# 4L60E_Controller_SMD_CONNECTOR.net
KiCad netlist of a schematic drawn in EAGLE
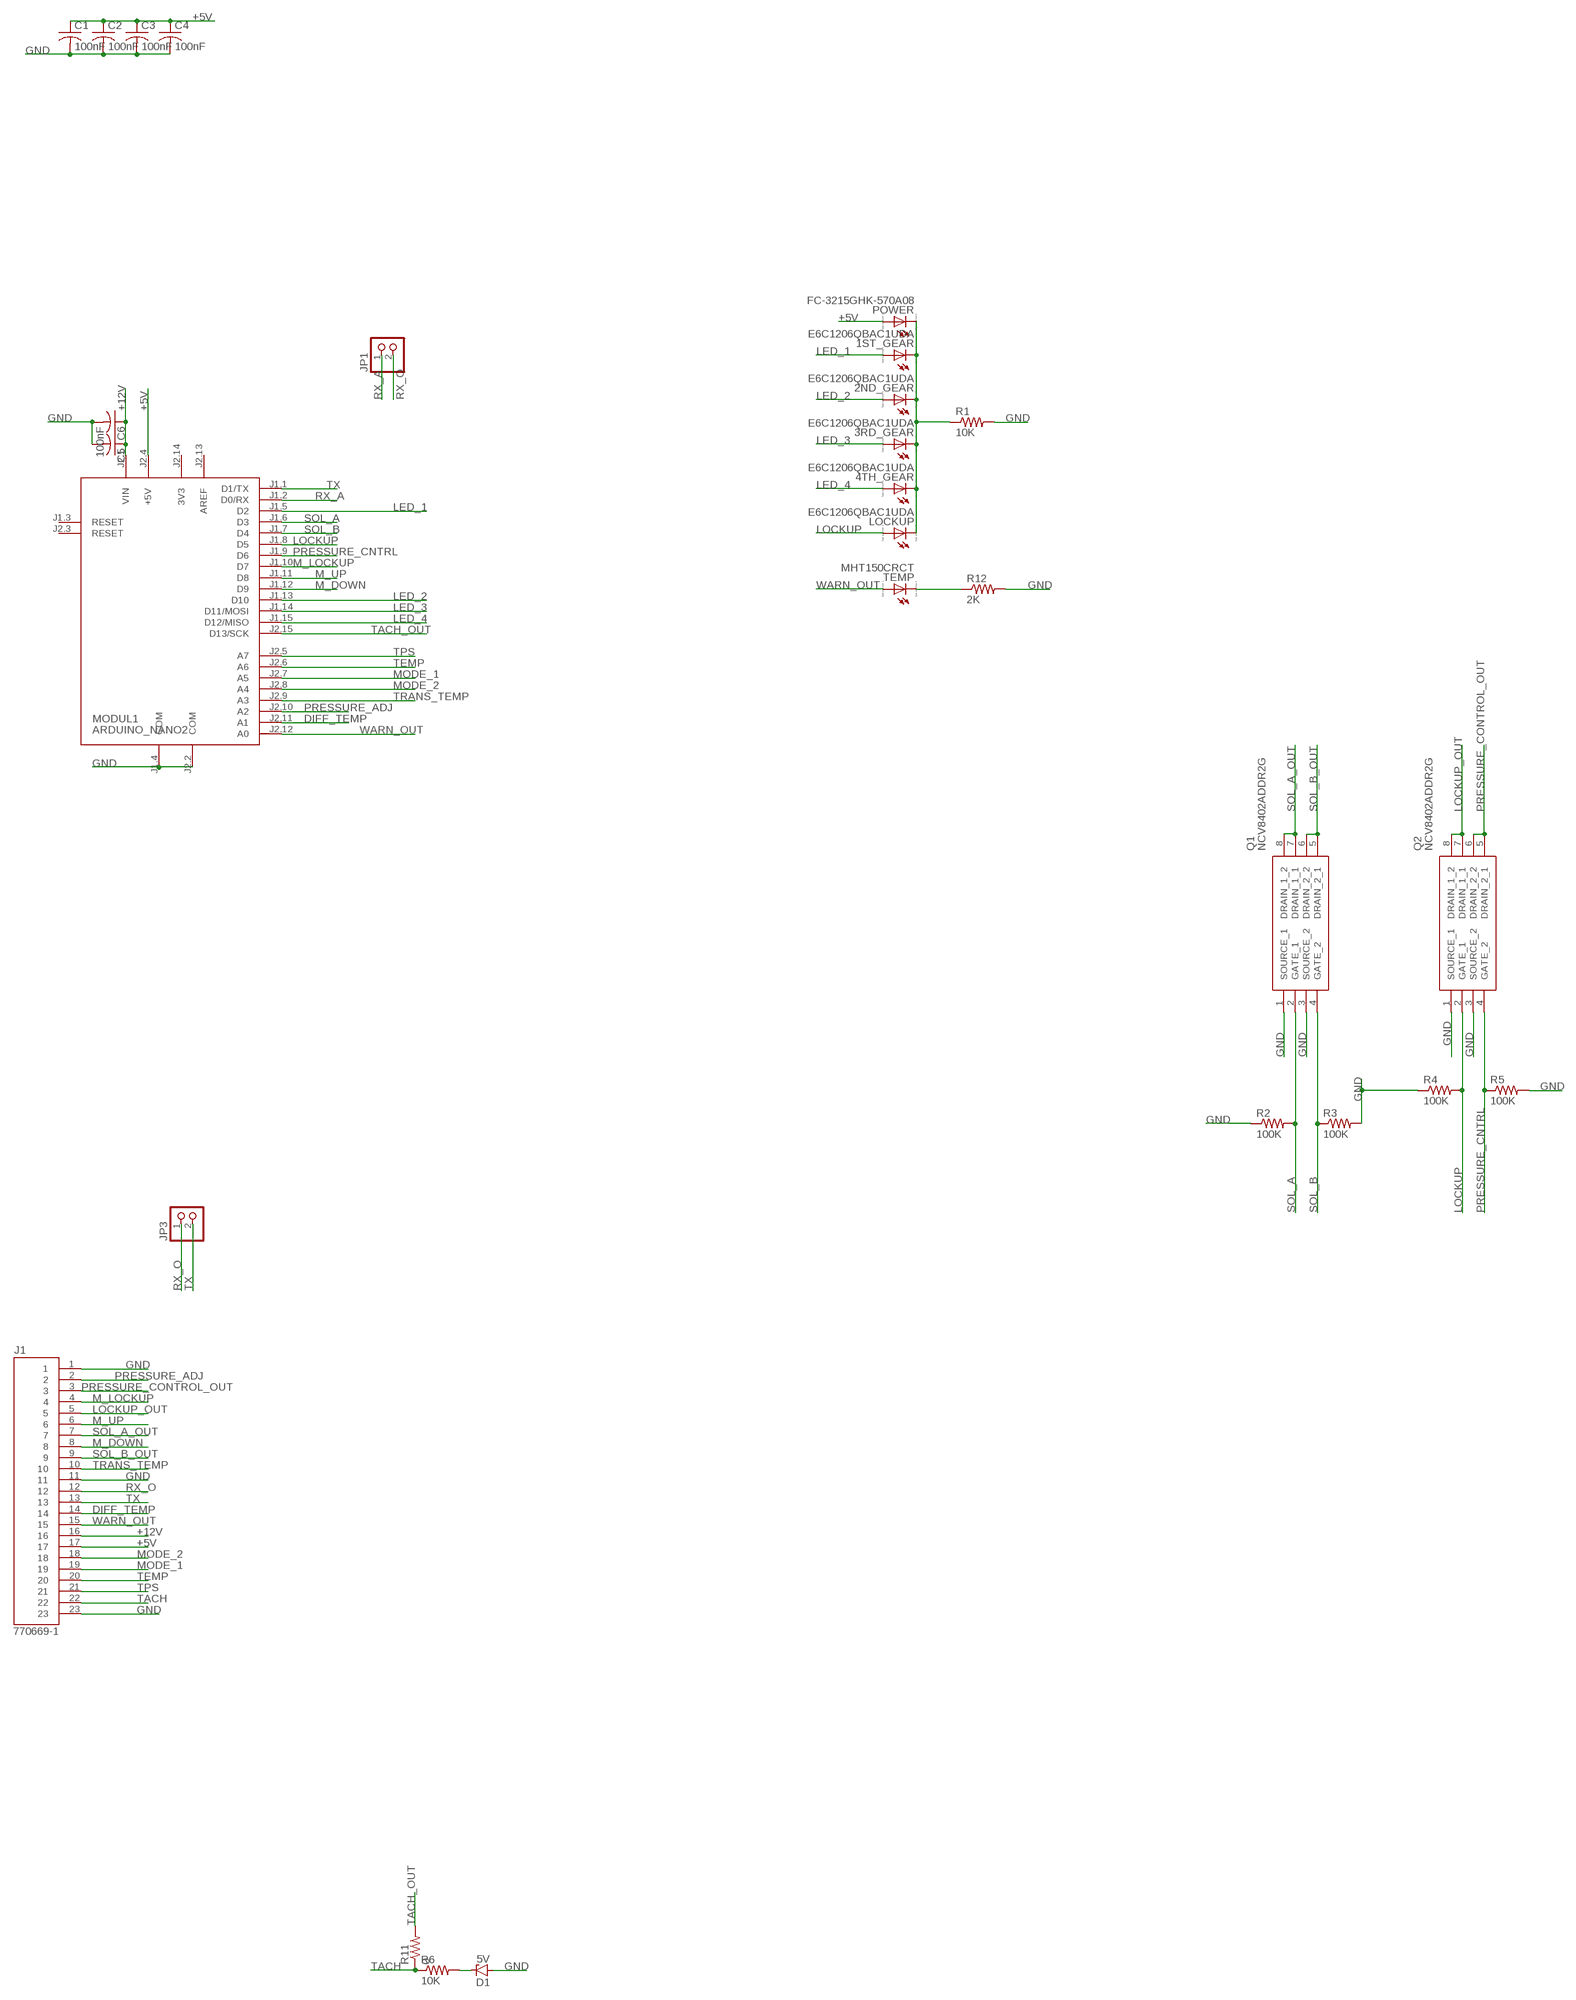
[diagram p0: schematic, sheet 1]

(export (version "E")
  (design (tool "Eeschema 10.0.6"))
  (components
    (comp (ref "1ST_GEAR")
      (value "E6C1206QBAC1UDA")
      (footprint "eagle-import:LED_1206")
      (libsource (lib "eagle-import") (part "LED_E"))
    )
    (comp (ref "2ND_GEAR")
      (value "E6C1206QBAC1UDA")
      (footprint "eagle-import:LED_1206")
      (libsource (lib "eagle-import") (part "LED_E"))
    )
    (comp (ref "3RD_GEAR")
      (value "E6C1206QBAC1UDA")
      (footprint "eagle-import:LED_1206")
      (libsource (lib "eagle-import") (part "LED_E"))
    )
    (comp (ref "4TH_GEAR")
      (value "E6C1206QBAC1UDA")
      (footprint "eagle-import:LED_1206")
      (libsource (lib "eagle-import") (part "LED_E"))
    )
    (comp (ref "C1")
      (value "100nF")
      (footprint "eagle-import:C0805")
      (libsource (lib "eagle-import") (part "C-USC0805"))
    )
    (comp (ref "C2")
      (value "100nF")
      (footprint "eagle-import:C0805")
      (libsource (lib "eagle-import") (part "C-USC0805"))
    )
    (comp (ref "C3")
      (value "100nF")
      (footprint "eagle-import:C0805")
      (libsource (lib "eagle-import") (part "C-USC0805"))
    )
    (comp (ref "C4")
      (value "100nF")
      (footprint "eagle-import:C0805")
      (libsource (lib "eagle-import") (part "C-USC0805"))
    )
    (comp (ref "C5")
      (value "C-USC1206")
      (footprint "eagle-import:C1206")
      (libsource (lib "eagle-import") (part "resistor_348_C-USC1206"))
    )
    (comp (ref "C6")
      (value "100nF")
      (footprint "eagle-import:C1206")
      (libsource (lib "eagle-import") (part "resistor_348_C-USC1206"))
    )
    (comp (ref "D1")
      (value "5V")
      (footprint "eagle-import:SOT23")
      (libsource (lib "eagle-import") (part "ZENER-DIODESOT23"))
    )
    (comp (ref "J1")
      (value "770669-1")
      (footprint "eagle-import:TE_770669-1")
      (fields (field (name "MF") "TE Connectivity"))
      (libsource (lib "eagle-import") (part "770669-1"))
    )
    (comp (ref "JP1")
      (value "PINHD-1X2")
      (footprint "eagle-import:1X02")
      (libsource (lib "eagle-import") (part "PINHD-1X2"))
    )
    (comp (ref "JP3")
      (value "PINHD-1X2")
      (footprint "eagle-import:1X02")
      (libsource (lib "eagle-import") (part "PINHD-1X2"))
    )
    (comp (ref "LOCKUP")
      (value "E6C1206QBAC1UDA")
      (footprint "eagle-import:LED_1206")
      (libsource (lib "eagle-import") (part "LED_E"))
    )
    (comp (ref "MODUL1")
      (value "ARDUINO_NANO2")
      (footprint "eagle-import:ARDUINO_NANO2")
      (libsource (lib "eagle-import") (part "ARDUINO_NANO2"))
    )
    (comp (ref "POWER")
      (value "FC-3215GHK-570A08")
      (footprint "eagle-import:LED_1206")
      (libsource (lib "eagle-import") (part "LED_E"))
    )
    (comp (ref "Q1")
      (value "NCV8402ADDR2G")
      (footprint "eagle-import:SOIC127P600X175-8N")
      (fields (field (name "MOUSER_PART_NUMBER") "863-NCV8402ADDR2G"))
      (libsource (lib "eagle-import") (part "NCV8402ADDR2G"))
    )
    (comp (ref "Q2")
      (value "NCV8402ADDR2G")
      (footprint "eagle-import:SOIC127P600X175-8N")
      (fields (field (name "MOUSER_PART_NUMBER") "863-NCV8402ADDR2G"))
      (libsource (lib "eagle-import") (part "NCV8402ADDR2G"))
    )
    (comp (ref "R1")
      (value "10K")
      (footprint "eagle-import:M0805")
      (libsource (lib "eagle-import") (part "resistor_348_R-US_M0805"))
    )
    (comp (ref "R2")
      (value "100K")
      (footprint "eagle-import:R0805")
      (libsource (lib "eagle-import") (part "R-US_R0805"))
    )
    (comp (ref "R3")
      (value "100K")
      (footprint "eagle-import:R0805")
      (libsource (lib "eagle-import") (part "R-US_R0805"))
    )
    (comp (ref "R4")
      (value "100K")
      (footprint "eagle-import:R0805")
      (libsource (lib "eagle-import") (part "R-US_R0805"))
    )
    (comp (ref "R5")
      (value "100K")
      (footprint "eagle-import:R0805")
      (libsource (lib "eagle-import") (part "R-US_R0805"))
    )
    (comp (ref "R6")
      (value "10K")
      (footprint "eagle-import:R0805")
      (libsource (lib "eagle-import") (part "resistor_348_R-US_R0805"))
    )
    (comp (ref "R11")
      (value "0")
      (footprint "eagle-import:R0805")
      (libsource (lib "eagle-import") (part "resistor_348_R-US_R0805"))
    )
    (comp (ref "R12")
      (value "2K")
      (footprint "eagle-import:R0805")
      (libsource (lib "eagle-import") (part "resistor_348_R-US_R0805"))
    )
    (comp (ref "TEMP")
      (value "MHT150CRCT")
      (footprint "eagle-import:LED_1206")
      (libsource (lib "eagle-import") (part "LED_E"))
    )
  )
  (nets
    (net (code "1") (name "/+5V") (class "Default")
      (node (ref "C1") (pin "1") (pinfunction "1_1") (pintype "passive"))
      (node (ref "C2") (pin "1") (pinfunction "1_1") (pintype "passive"))
      (node (ref "C3") (pin "1") (pinfunction "1_1") (pintype "passive"))
      (node (ref "C4") (pin "1") (pinfunction "1_1") (pintype "passive"))
      (node (ref "J1") (pin "17") (pinfunction "17_17") (pintype "passive"))
      (node (ref "MODUL1") (pin "J2.4") (pinfunction "+5V_J2.4") (pintype "power_in"))
      (node (ref "POWER") (pin "A") (pinfunction "A_A") (pintype "passive"))
    )
    (net (code "2") (name "/+12V") (class "Default")
      (node (ref "C5") (pin "1") (pinfunction "1_1") (pintype "passive"))
      (node (ref "C6") (pin "1") (pinfunction "1_1") (pintype "passive"))
      (node (ref "J1") (pin "16") (pinfunction "16_16") (pintype "passive"))
      (node (ref "MODUL1") (pin "J2.1") (pinfunction "VIN_J2.1") (pintype "power_in"))
    )
    (net (code "3") (name "/3V3") (class "Default")
      (node (ref "MODUL1") (pin "J2.14") (pinfunction "3V3_J2.14") (pintype "power_in"))
    )
    (net (code "4") (name "/AREF") (class "Default")
      (node (ref "MODUL1") (pin "J2.13") (pinfunction "AREF_J2.13") (pintype "power_in"))
    )
    (net (code "5") (name "/DIFF_TEMP") (class "Default")
      (node (ref "J1") (pin "14") (pinfunction "14_14") (pintype "passive"))
      (node (ref "MODUL1") (pin "J2.11") (pinfunction "A1_J2.11") (pintype "bidirectional"))
    )
    (net (code "6") (name "/GND") (class "Default")
      (node (ref "C1") (pin "2") (pinfunction "2_2") (pintype "passive"))
      (node (ref "C2") (pin "2") (pinfunction "2_2") (pintype "passive"))
      (node (ref "C3") (pin "2") (pinfunction "2_2") (pintype "passive"))
      (node (ref "C4") (pin "2") (pinfunction "2_2") (pintype "passive"))
      (node (ref "C5") (pin "2") (pinfunction "2_2") (pintype "passive"))
      (node (ref "C6") (pin "2") (pinfunction "2_2") (pintype "passive"))
      (node (ref "D1") (pin "1") (pinfunction "A_1") (pintype "passive"))
      (node (ref "J1") (pin "1") (pinfunction "1_1") (pintype "passive"))
      (node (ref "J1") (pin "11") (pinfunction "11_11") (pintype "passive"))
      (node (ref "J1") (pin "23") (pinfunction "23_23") (pintype "passive"))
      (node (ref "MODUL1") (pin "J1.4") (pinfunction "COM_J1.4") (pintype "power_in"))
      (node (ref "MODUL1") (pin "J2.2") (pinfunction "COM_J2.2") (pintype "power_in"))
      (node (ref "Q1") (pin "1") (pinfunction "SOURCE_1_1") (pintype "bidirectional"))
      (node (ref "Q1") (pin "3") (pinfunction "SOURCE_2_3") (pintype "bidirectional"))
      (node (ref "Q2") (pin "1") (pinfunction "SOURCE_1_1") (pintype "bidirectional"))
      (node (ref "Q2") (pin "3") (pinfunction "SOURCE_2_3") (pintype "bidirectional"))
      (node (ref "R1") (pin "2") (pinfunction "2_2") (pintype "passive"))
      (node (ref "R12") (pin "2") (pinfunction "2_2") (pintype "passive"))
      (node (ref "R2") (pin "1") (pinfunction "1_1") (pintype "passive"))
      (node (ref "R3") (pin "2") (pinfunction "2_2") (pintype "passive"))
      (node (ref "R4") (pin "1") (pinfunction "1_1") (pintype "passive"))
      (node (ref "R5") (pin "2") (pinfunction "2_2") (pintype "passive"))
    )
    (net (code "7") (name "/LED_1") (class "Default")
      (node (ref "1ST_GEAR") (pin "A") (pinfunction "A_A") (pintype "passive"))
      (node (ref "MODUL1") (pin "J1.5") (pinfunction "D2_J1.5") (pintype "bidirectional"))
    )
    (net (code "8") (name "/LED_2") (class "Default")
      (node (ref "2ND_GEAR") (pin "A") (pinfunction "A_A") (pintype "passive"))
      (node (ref "MODUL1") (pin "J1.13") (pinfunction "D10_J1.13") (pintype "bidirectional"))
    )
    (net (code "9") (name "/LED_3") (class "Default")
      (node (ref "3RD_GEAR") (pin "A") (pinfunction "A_A") (pintype "passive"))
      (node (ref "MODUL1") (pin "J1.14") (pinfunction "D11/MOSI_J1.14") (pintype "bidirectional"))
    )
    (net (code "10") (name "/LED_4") (class "Default")
      (node (ref "4TH_GEAR") (pin "A") (pinfunction "A_A") (pintype "passive"))
      (node (ref "MODUL1") (pin "J1.15") (pinfunction "D12/MISO_J1.15") (pintype "bidirectional"))
    )
    (net (code "11") (name "/LOCKUP") (class "Default")
      (node (ref "LOCKUP") (pin "A") (pinfunction "A_A") (pintype "passive"))
      (node (ref "MODUL1") (pin "J1.8") (pinfunction "D5_J1.8") (pintype "bidirectional"))
      (node (ref "Q2") (pin "2") (pinfunction "GATE_1_2") (pintype "bidirectional"))
      (node (ref "R4") (pin "2") (pinfunction "2_2") (pintype "passive"))
    )
    (net (code "12") (name "/LOCKUP_OUT") (class "Default")
      (node (ref "J1") (pin "5") (pinfunction "5_5") (pintype "passive"))
      (node (ref "Q2") (pin "7") (pinfunction "DRAIN_1_1_7") (pintype "bidirectional"))
      (node (ref "Q2") (pin "8") (pinfunction "DRAIN_1_2_8") (pintype "bidirectional"))
    )
    (net (code "13") (name "/MODE_1") (class "Default")
      (node (ref "J1") (pin "19") (pinfunction "19_19") (pintype "passive"))
      (node (ref "MODUL1") (pin "J2.7") (pinfunction "A5_J2.7") (pintype "bidirectional"))
    )
    (net (code "14") (name "/MODE_2") (class "Default")
      (node (ref "J1") (pin "18") (pinfunction "18_18") (pintype "passive"))
      (node (ref "MODUL1") (pin "J2.8") (pinfunction "A4_J2.8") (pintype "bidirectional"))
    )
    (net (code "15") (name "/M_DOWN") (class "Default")
      (node (ref "J1") (pin "8") (pinfunction "8_8") (pintype "passive"))
      (node (ref "MODUL1") (pin "J1.12") (pinfunction "D9_J1.12") (pintype "bidirectional"))
    )
    (net (code "16") (name "/M_LOCKUP") (class "Default")
      (node (ref "J1") (pin "4") (pinfunction "4_4") (pintype "passive"))
      (node (ref "MODUL1") (pin "J1.10") (pinfunction "D7_J1.10") (pintype "bidirectional"))
    )
    (net (code "17") (name "/M_UP") (class "Default")
      (node (ref "J1") (pin "6") (pinfunction "6_6") (pintype "passive"))
      (node (ref "MODUL1") (pin "J1.11") (pinfunction "D8_J1.11") (pintype "bidirectional"))
    )
    (net (code "18") (name "/PRESSURE_ADJ") (class "Default")
      (node (ref "J1") (pin "2") (pinfunction "2_2") (pintype "passive"))
      (node (ref "MODUL1") (pin "J2.10") (pinfunction "A2_J2.10") (pintype "bidirectional"))
    )
    (net (code "19") (name "/PRESSURE_CNTRL") (class "Default")
      (node (ref "MODUL1") (pin "J1.9") (pinfunction "D6_J1.9") (pintype "bidirectional"))
      (node (ref "Q2") (pin "4") (pinfunction "GATE_2_4") (pintype "bidirectional"))
      (node (ref "R5") (pin "1") (pinfunction "1_1") (pintype "passive"))
    )
    (net (code "20") (name "/PRESSURE_CONTROL_OUT") (class "Default")
      (node (ref "J1") (pin "3") (pinfunction "3_3") (pintype "passive"))
      (node (ref "Q2") (pin "5") (pinfunction "DRAIN_2_1_5") (pintype "bidirectional"))
      (node (ref "Q2") (pin "6") (pinfunction "DRAIN_2_2_6") (pintype "bidirectional"))
    )
    (net (code "21") (name "/RX_A") (class "Default")
      (node (ref "JP1") (pin "1") (pinfunction "1_1") (pintype "passive"))
      (node (ref "MODUL1") (pin "J1.2") (pinfunction "D0/RX_J1.2") (pintype "bidirectional"))
    )
    (net (code "22") (name "/RX_O") (class "Default")
      (node (ref "J1") (pin "12") (pinfunction "12_12") (pintype "passive"))
      (node (ref "JP1") (pin "2") (pinfunction "2_2") (pintype "passive"))
      (node (ref "JP3") (pin "1") (pinfunction "1_1") (pintype "passive"))
    )
    (net (code "23") (name "/SOL_A") (class "Default")
      (node (ref "MODUL1") (pin "J1.6") (pinfunction "D3_J1.6") (pintype "bidirectional"))
      (node (ref "Q1") (pin "2") (pinfunction "GATE_1_2") (pintype "bidirectional"))
      (node (ref "R2") (pin "2") (pinfunction "2_2") (pintype "passive"))
    )
    (net (code "24") (name "/SOL_A_OUT") (class "Default")
      (node (ref "J1") (pin "7") (pinfunction "7_7") (pintype "passive"))
      (node (ref "Q1") (pin "7") (pinfunction "DRAIN_1_1_7") (pintype "bidirectional"))
      (node (ref "Q1") (pin "8") (pinfunction "DRAIN_1_2_8") (pintype "bidirectional"))
    )
    (net (code "25") (name "/SOL_B") (class "Default")
      (node (ref "MODUL1") (pin "J1.7") (pinfunction "D4_J1.7") (pintype "bidirectional"))
      (node (ref "Q1") (pin "4") (pinfunction "GATE_2_4") (pintype "bidirectional"))
      (node (ref "R3") (pin "1") (pinfunction "1_1") (pintype "passive"))
    )
    (net (code "26") (name "/SOL_B_OUT") (class "Default")
      (node (ref "J1") (pin "9") (pinfunction "9_9") (pintype "passive"))
      (node (ref "Q1") (pin "5") (pinfunction "DRAIN_2_1_5") (pintype "bidirectional"))
      (node (ref "Q1") (pin "6") (pinfunction "DRAIN_2_2_6") (pintype "bidirectional"))
    )
    (net (code "27") (name "/TACH") (class "Default")
      (node (ref "J1") (pin "22") (pinfunction "22_22") (pintype "passive"))
      (node (ref "R11") (pin "1") (pinfunction "1_1") (pintype "passive"))
      (node (ref "R6") (pin "1") (pinfunction "1_1") (pintype "passive"))
    )
    (net (code "28") (name "/TACH_OUT") (class "Default")
      (node (ref "MODUL1") (pin "J2.15") (pinfunction "D13/SCK_J2.15") (pintype "bidirectional"))
      (node (ref "R11") (pin "2") (pinfunction "2_2") (pintype "passive"))
    )
    (net (code "29") (name "/TEMP") (class "Default")
      (node (ref "J1") (pin "20") (pinfunction "20_20") (pintype "passive"))
      (node (ref "MODUL1") (pin "J2.6") (pinfunction "A6_J2.6") (pintype "bidirectional"))
    )
    (net (code "30") (name "/TPS") (class "Default")
      (node (ref "J1") (pin "21") (pinfunction "21_21") (pintype "passive"))
      (node (ref "MODUL1") (pin "J2.5") (pinfunction "A7_J2.5") (pintype "bidirectional"))
    )
    (net (code "31") (name "/TRANS_TEMP") (class "Default")
      (node (ref "J1") (pin "10") (pinfunction "10_10") (pintype "passive"))
      (node (ref "MODUL1") (pin "J2.9") (pinfunction "A3_J2.9") (pintype "bidirectional"))
    )
    (net (code "32") (name "/TX") (class "Default")
      (node (ref "J1") (pin "13") (pinfunction "13_13") (pintype "passive"))
      (node (ref "JP3") (pin "2") (pinfunction "2_2") (pintype "passive"))
      (node (ref "MODUL1") (pin "J1.1") (pinfunction "D1/TX_J1.1") (pintype "bidirectional"))
    )
    (net (code "33") (name "/WARN_OUT") (class "Default")
      (node (ref "J1") (pin "15") (pinfunction "15_15") (pintype "passive"))
      (node (ref "MODUL1") (pin "J2.12") (pinfunction "A0_J2.12") (pintype "bidirectional"))
      (node (ref "TEMP") (pin "A") (pinfunction "A_A") (pintype "passive"))
    )
    (net (code "34") (name "Net-(1ST_GEAR-PadC)") (class "Default")
      (node (ref "1ST_GEAR") (pin "C") (pinfunction "C_C") (pintype "passive"))
      (node (ref "2ND_GEAR") (pin "C") (pinfunction "C_C") (pintype "passive"))
      (node (ref "3RD_GEAR") (pin "C") (pinfunction "C_C") (pintype "passive"))
      (node (ref "4TH_GEAR") (pin "C") (pinfunction "C_C") (pintype "passive"))
      (node (ref "LOCKUP") (pin "C") (pinfunction "C_C") (pintype "passive"))
      (node (ref "POWER") (pin "C") (pinfunction "C_C") (pintype "passive"))
      (node (ref "R1") (pin "1") (pinfunction "1_1") (pintype "passive"))
    )
    (net (code "35") (name "Net-(D1-C)") (class "Default")
      (node (ref "D1") (pin "3") (pinfunction "C_3") (pintype "passive"))
      (node (ref "R6") (pin "2") (pinfunction "2_2") (pintype "passive"))
    )
    (net (code "36") (name "Net-(R12-Pad1)") (class "Default")
      (node (ref "R12") (pin "1") (pinfunction "1_1") (pintype "passive"))
      (node (ref "TEMP") (pin "C") (pinfunction "C_C") (pintype "passive"))
    )
    (net (code "37") (name "unconnected-(MODUL1-RESET-PadJ1.3)") (class "Default")
      (node (ref "MODUL1") (pin "J1.3") (pinfunction "RESET_J1.3") (pintype "bidirectional"))
    )
    (net (code "38") (name "unconnected-(MODUL1-RESET-PadJ2.3)") (class "Default")
      (node (ref "MODUL1") (pin "J2.3") (pinfunction "RESET_J2.3") (pintype "bidirectional"))
    )
  )
)
